# BMS_Controler.net
KiCad netlist of a schematic drawn in Altium Designer
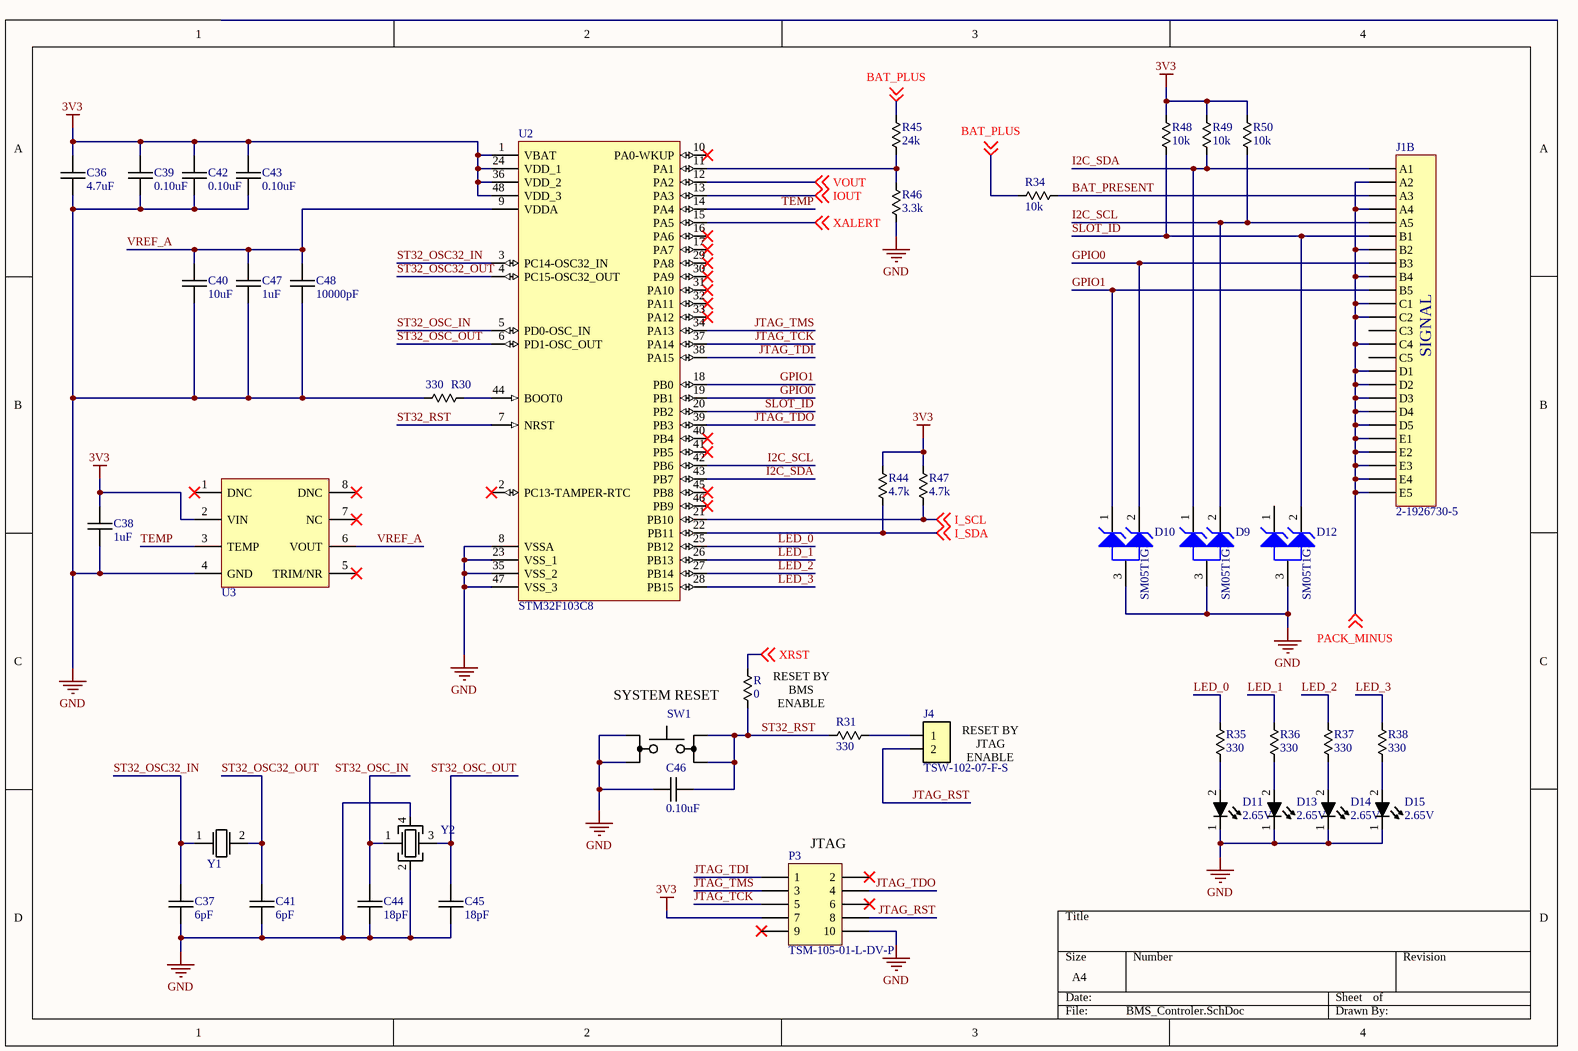
[diagram p0: BMS_Controler.SchDoc]

(export (version "E")
  (design (tool "Eeschema 10.0.6"))
  (components
    (comp (ref "C36")
      (value "4.7uF")
      (footprint "chip_0805")
      (description "CAP, 4.7uF, 10%, 25V, X7R, 0805")
      (fields (field (name "PART NUMBER") "CAP-00128") (field (name "TOLERANCE") "10%"))
      (libsource (lib "Capacitors$") (part "CAP-00128"))
    )
    (comp (ref "C37")
      (value "6pF")
      (footprint "chip_0603")
      (description "CAP, 6pF, ±10%, 50V, C0G, 0603")
      (fields (field (name "PART NUMBER") "CAP-00538") (field (name "TOLERANCE") "±10%"))
      (libsource (lib "Capacitors$") (part "CAP-00538"))
    )
    (comp (ref "C38")
      (value "1uF")
      (footprint "chip_0805")
      (description "CAP, 1uF, 10%, 50V, X7R, 0805")
      (fields (field (name "PART NUMBER") "CAP-00109") (field (name "TOLERANCE") "10%"))
      (libsource (lib "Capacitors$") (part "CAP-00109"))
    )
    (comp (ref "C39")
      (value "0.10uF")
      (footprint "chip_0805")
      (description "CAP, 0.10uF, 10%, 50V, X7R, 0805")
      (fields (field (name "PART NUMBER") "CAP-00072") (field (name "TOLERANCE") "10%"))
      (libsource (lib "Capacitors$") (part "CAP-00072"))
    )
    (comp (ref "C40")
      (value "10uF")
      (footprint "chip_0805")
      (description "CAP, 10uF, 10%, 10V, X7R, 0805")
      (fields (field (name "PART NUMBER") "CAP-00131") (field (name "TOLERANCE") "10%"))
      (libsource (lib "Capacitors$") (part "CAP-00131"))
    )
    (comp (ref "C41")
      (value "6pF")
      (footprint "chip_0603")
      (description "CAP, 6pF, ±10%, 50V, C0G, 0603")
      (fields (field (name "PART NUMBER") "CAP-00538") (field (name "TOLERANCE") "±10%"))
      (libsource (lib "Capacitors$") (part "CAP-00538"))
    )
    (comp (ref "C42")
      (value "0.10uF")
      (footprint "chip_0805")
      (description "CAP, 0.10uF, 10%, 50V, X7R, 0805")
      (fields (field (name "PART NUMBER") "CAP-00072") (field (name "TOLERANCE") "10%"))
      (libsource (lib "Capacitors$") (part "CAP-00072"))
    )
    (comp (ref "C43")
      (value "0.10uF")
      (footprint "chip_0805")
      (description "CAP, 0.10uF, 10%, 50V, X7R, 0805")
      (fields (field (name "PART NUMBER") "CAP-00072") (field (name "TOLERANCE") "10%"))
      (libsource (lib "Capacitors$") (part "CAP-00072"))
    )
    (comp (ref "C44")
      (value "18pF")
      (footprint "chip_0603")
      (description "CAP, 18pF, ±1%, 50V, C0G, 0603")
      (fields (field (name "PART NUMBER") "CAP-00417") (field (name "TOLERANCE") "±1%"))
      (libsource (lib "Capacitors$") (part "CAP-00417"))
    )
    (comp (ref "C45")
      (value "18pF")
      (footprint "chip_0603")
      (description "CAP, 18pF, ±1%, 50V, C0G, 0603")
      (fields (field (name "PART NUMBER") "CAP-00417") (field (name "TOLERANCE") "±1%"))
      (libsource (lib "Capacitors$") (part "CAP-00417"))
    )
    (comp (ref "C46")
      (value "0.10uF")
      (footprint "chip_0805")
      (description "CAP, 0.10uF, 10%, 50V, X7R, 0805")
      (fields (field (name "PART NUMBER") "CAP-00072") (field (name "TOLERANCE") "10%"))
      (libsource (lib "Capacitors$") (part "CAP-00072"))
    )
    (comp (ref "C47")
      (value "1uF")
      (footprint "chip_0805")
      (description "CAP, 1uF, 10%, 50V, X7R, 0805")
      (fields (field (name "PART NUMBER") "CAP-00109") (field (name "TOLERANCE") "10%"))
      (libsource (lib "Capacitors$") (part "CAP-00109"))
    )
    (comp (ref "C48")
      (value "10000pF")
      (footprint "chip_0805")
      (description "CAP, 10000pF, 10%, 25V, X7R, 0805")
      (fields (field (name "PART NUMBER") "CAP-00045") (field (name "TOLERANCE") "10%"))
      (libsource (lib "Capacitors$") (part "CAP-00045"))
    )
    (comp (ref "D9")
      (value "SM05T1G")
      (footprint "ONSC-SOT-23-3-318-08_V")
      (fields (field (name "MANUFACTURER") "On Semiconductor"))
      (libsource (lib "Altium Content Vault") (part "ONSC-K1K2A3-3"))
    )
    (comp (ref "D10")
      (value "SM05T1G")
      (footprint "ONSC-SOT-23-3-318-08_V")
      (fields (field (name "MANUFACTURER") "On Semiconductor"))
      (libsource (lib "Altium Content Vault") (part "ONSC-K1K2A3-3"))
    )
    (comp (ref "D11")
      (value "2.65V")
      (footprint "APA2107")
      (description "LED, Green, SMD Right-Angle, Low-Current, Kingbright HELI2 Series")
      (fields (field (name "PART NUMBER") "DIO-00083") (field (name "MANUFACTURER") "Kingbright"))
      (libsource (lib "Diodes$") (part "DIO-00083"))
    )
    (comp (ref "D12")
      (value "SM05T1G")
      (footprint "ONSC-SOT-23-3-318-08_V")
      (fields (field (name "MANUFACTURER") "On Semiconductor"))
      (libsource (lib "Altium Content Vault") (part "ONSC-K1K2A3-3"))
    )
    (comp (ref "D13")
      (value "2.65V")
      (footprint "APA2107")
      (description "LED, Green, SMD Right-Angle, Low-Current, Kingbright HELI2 Series")
      (fields (field (name "PART NUMBER") "DIO-00083") (field (name "MANUFACTURER") "Kingbright"))
      (libsource (lib "Diodes$") (part "DIO-00083"))
    )
    (comp (ref "D14")
      (value "2.65V")
      (footprint "APA2107")
      (description "LED, Green, SMD Right-Angle, Low-Current, Kingbright HELI2 Series")
      (fields (field (name "PART NUMBER") "DIO-00083") (field (name "MANUFACTURER") "Kingbright"))
      (libsource (lib "Diodes$") (part "DIO-00083"))
    )
    (comp (ref "D15")
      (value "2.65V")
      (footprint "APA2107")
      (description "LED, Green, SMD Right-Angle, Low-Current, Kingbright HELI2 Series")
      (fields (field (name "PART NUMBER") "DIO-00083") (field (name "MANUFACTURER") "Kingbright"))
      (libsource (lib "Diodes$") (part "DIO-00083"))
    )
    (comp (ref "J1")
      (value "2-1926730-5")
      (footprint "TE_CONN_2-1926730-5")
      (description "Backplane Header, Blades and Pins, Edge Mount Right Angle, 10 Power 25 Signal")
      (fields (field (name "PART NUMBER") "CONN-00093") (field (name "MANUFACTURER") "TE Connectivity"))
      (libsource (lib "Connectors$") (part "CONN-00093"))
    )
    (comp (ref "J4")
      (value "TSW-102-07-F-S")
      (footprint "HDDR_2x1_0")
      (description "Header, 2x1, 0.1\"")
      (fields (field (name "PART NUMBER") "CONN-00055") (field (name "MANUFACTURER") "Samtec"))
      (libsource (lib "Connectors$") (part "CONN-00055"))
    )
    (comp (ref "P3")
      (value "TSM-105-01-L-DV-P")
      (footprint "SAMTEC_SMD_HDDR_5x2")
      (description "Header, 5x2, 0.1\", SMD")
      (fields (field (name "PART NUMBER") "CONN-00071") (field (name "MANUFACTURER") "Samtec"))
      (libsource (lib "Connectors$") (part "CONN-00071"))
    )
    (comp (ref "R30")
      (value "330")
      (footprint "chip_0805")
      (description "RES SMD 330 OHM 1% 1/8W 0805")
      (fields (field (name "PART NUMBER") "RES-00222") (field (name "TOLERANCE") "1%"))
      (libsource (lib "Resistors$") (part "RES-00222"))
    )
    (comp (ref "R31")
      (value "330")
      (footprint "chip_0805")
      (description "RES SMD 330 OHM 1% 1/8W 0805")
      (fields (field (name "PART NUMBER") "RES-00222") (field (name "TOLERANCE") "1%"))
      (libsource (lib "Resistors$") (part "RES-00222"))
    )
    (comp (ref "R34")
      (value "10k")
      (footprint "chip_0805")
      (description "RES SMD 10K OHM 1% 1/8W 0805")
      (fields (field (name "PART NUMBER") "RES-00307") (field (name "TOLERANCE") "1%"))
      (libsource (lib "Resistors$") (part "RES-00307"))
    )
    (comp (ref "R35")
      (value "330")
      (footprint "chip_0805")
      (description "RES SMD 330 OHM 1% 1/8W 0805")
      (fields (field (name "PART NUMBER") "RES-00222") (field (name "TOLERANCE") "1%"))
      (libsource (lib "Resistors$") (part "RES-00222"))
    )
    (comp (ref "R36")
      (value "330")
      (footprint "chip_0805")
      (description "RES SMD 330 OHM 1% 1/8W 0805")
      (fields (field (name "PART NUMBER") "RES-00222") (field (name "TOLERANCE") "1%"))
      (libsource (lib "Resistors$") (part "RES-00222"))
    )
    (comp (ref "R37")
      (value "330")
      (footprint "chip_0805")
      (description "RES SMD 330 OHM 1% 1/8W 0805")
      (fields (field (name "PART NUMBER") "RES-00222") (field (name "TOLERANCE") "1%"))
      (libsource (lib "Resistors$") (part "RES-00222"))
    )
    (comp (ref "R38")
      (value "330")
      (footprint "chip_0805")
      (description "RES SMD 330 OHM 1% 1/8W 0805")
      (fields (field (name "PART NUMBER") "RES-00222") (field (name "TOLERANCE") "1%"))
      (libsource (lib "Resistors$") (part "RES-00222"))
    )
    (comp (ref "R43")
      (value "0")
      (footprint "chip_0805")
      (description "RES SMD 0 OHM 1/8W 0805 Thick Film")
      (fields (field (name "PART NUMBER") "RES-00720") (field (name "TOLERANCE") "Jumper"))
      (libsource (lib "Resistors$") (part "RES-00720"))
    )
    (comp (ref "R44")
      (value "4.7k")
      (footprint "chip_0805")
      (description "RES SMD 4.7K OHM 1% 1/8W 0805")
      (fields (field (name "PART NUMBER") "RES-00471") (field (name "TOLERANCE") "1%"))
      (libsource (lib "Resistors$") (part "RES-00471"))
    )
    (comp (ref "R45")
      (value "24k")
      (footprint "chip_0805")
      (description "RES SMD 24K OHM 1% 1/8W 0805")
      (fields (field (name "PART NUMBER") "RES-00400") (field (name "TOLERANCE") "1%"))
      (libsource (lib "Resistors$") (part "RES-00400"))
    )
    (comp (ref "R46")
      (value "3.3k")
      (footprint "chip_0805")
      (description "RES SMD 3.3K OHM 1% 1/8W 0805")
      (fields (field (name "PART NUMBER") "RES-00420") (field (name "TOLERANCE") "1%"))
      (libsource (lib "Resistors$") (part "RES-00420"))
    )
    (comp (ref "R47")
      (value "4.7k")
      (footprint "chip_0805")
      (description "RES SMD 4.7K OHM 1% 1/8W 0805")
      (fields (field (name "PART NUMBER") "RES-00471") (field (name "TOLERANCE") "1%"))
      (libsource (lib "Resistors$") (part "RES-00471"))
    )
    (comp (ref "R48")
      (value "10k")
      (footprint "chip_0805")
      (description "RES SMD 10K OHM 1% 1/8W 0805")
      (fields (field (name "PART NUMBER") "RES-00307") (field (name "TOLERANCE") "1%"))
      (libsource (lib "Resistors$") (part "RES-00307"))
    )
    (comp (ref "R49")
      (value "10k")
      (footprint "chip_0805")
      (description "RES SMD 10K OHM 1% 1/8W 0805")
      (fields (field (name "PART NUMBER") "RES-00307") (field (name "TOLERANCE") "1%"))
      (libsource (lib "Resistors$") (part "RES-00307"))
    )
    (comp (ref "R50")
      (value "10k")
      (footprint "chip_0805")
      (description "RES SMD 10K OHM 1% 1/8W 0805")
      (fields (field (name "PART NUMBER") "RES-00307") (field (name "TOLERANCE") "1%"))
      (libsource (lib "Resistors$") (part "RES-00307"))
    )
    (comp (ref "SW1")
      (value "SW_1P1T_2")
      (footprint "B3FS-1000")
      (description "Switch, SPST-NO, Tactile, 6.3x6.0mm, SMD, 50mA 24VDC")
      (fields (field (name "PART NUMBER") "MISC-00042") (field (name "MANUFACTURER") "Omron"))
      (libsource (lib "Misc$") (part "MISC-00042"))
    )
    (comp (ref "U2")
      (value "STM32F103C8")
      (footprint "LQFP48_0")
      (description "STM32 M3, LQFP-48")
      (fields (field (name "PART NUMBER") "UCTRL-00008") (field (name "MANUFACTURER") "ST"))
      (libsource (lib "Microcontrollers$") (part "UCTRL-00008"))
    )
    (comp (ref "U3")
      (value "REF50xx")
      (footprint "SO-8_1")
      (description "IC, Voltage Reference, 2.5V, 3ppm/°C, REF5020")
      (fields (field (name "PART NUMBER") "ANLG-00055") (field (name "MANUFACTURER") "TI"))
      (libsource (lib "Analog$") (part "ANLG-00055"))
    )
    (comp (ref "Y1")
      (value "osc_xtal_2p_0")
      (footprint "ABS25_OSC")
      (description "XTAL, 32.768kHz, 6pF, 20ppm")
      (fields (field (name "PART NUMBER") "OSC-00003") (field (name "TOLERANCE") "20ppm"))
      (libsource (lib "Oscillators$") (part "OSC-00003"))
    )
    (comp (ref "Y2")
      (value "osc_xtal_4p_1-3")
      (footprint "ECX-53B")
      (description "XTAL, 8MHz, 10pF, 10ppm")
      (fields (field (name "PART NUMBER") "OSC-00006") (field (name "TOLERANCE") "10ppm"))
      (libsource (lib "Oscillators$") (part "OSC-00006"))
    )
  )
  (nets
    (net (code "1") (name "/BAT_PRESENT") (class "Default")
      (node (ref "J1") (pin "A3") (pinfunction "A3_A3") (pintype "passive"))
      (node (ref "R34") (pin "2") (pinfunction "2_2") (pintype "passive"))
    )
    (net (code "2") (name "/GPIO0") (class "Default")
      (node (ref "D10") (pin "2") (pinfunction "K2_2") (pintype "passive"))
      (node (ref "J1") (pin "B3") (pinfunction "B3_B3") (pintype "passive"))
      (node (ref "U2") (pin "19") (pinfunction "PB1_19") (pintype "bidirectional"))
    )
    (net (code "3") (name "/GPIO1") (class "Default")
      (node (ref "D10") (pin "1") (pinfunction "K1_1") (pintype "passive"))
      (node (ref "J1") (pin "B5") (pinfunction "B5_B5") (pintype "passive"))
      (node (ref "U2") (pin "18") (pinfunction "PB0_18") (pintype "bidirectional"))
    )
    (net (code "4") (name "/I2C_SCL") (class "Default")
      (node (ref "D9") (pin "2") (pinfunction "K2_2") (pintype "passive"))
      (node (ref "J1") (pin "A5") (pinfunction "A5_A5") (pintype "passive"))
      (node (ref "R50") (pin "1") (pinfunction "1_1") (pintype "passive"))
      (node (ref "U2") (pin "42") (pinfunction "PB6_42") (pintype "bidirectional"))
    )
    (net (code "5") (name "/I2C_SDA") (class "Default")
      (node (ref "D9") (pin "1") (pinfunction "K1_1") (pintype "passive"))
      (node (ref "J1") (pin "A1") (pinfunction "A1_A1") (pintype "passive"))
      (node (ref "R49") (pin "1") (pinfunction "1_1") (pintype "passive"))
      (node (ref "U2") (pin "43") (pinfunction "PB7_43") (pintype "bidirectional"))
    )
    (net (code "6") (name "/JTAG_RST") (class "Default")
      (node (ref "J4") (pin "2") (pinfunction "2_2") (pintype "passive"))
      (node (ref "P3") (pin "8") (pinfunction "8_8") (pintype "passive"))
    )
    (net (code "7") (name "/JTAG_TCK") (class "Default")
      (node (ref "P3") (pin "5") (pinfunction "5_5") (pintype "passive"))
      (node (ref "U2") (pin "37") (pinfunction "PA14_37") (pintype "bidirectional"))
    )
    (net (code "8") (name "/JTAG_TDI") (class "Default")
      (node (ref "P3") (pin "1") (pinfunction "1_1") (pintype "passive"))
      (node (ref "U2") (pin "38") (pinfunction "PA15_38") (pintype "bidirectional"))
    )
    (net (code "9") (name "/JTAG_TDO") (class "Default")
      (node (ref "P3") (pin "4") (pinfunction "4_4") (pintype "passive"))
      (node (ref "U2") (pin "39") (pinfunction "PB3_39") (pintype "bidirectional"))
    )
    (net (code "10") (name "/JTAG_TMS") (class "Default")
      (node (ref "P3") (pin "3") (pinfunction "3_3") (pintype "passive"))
      (node (ref "U2") (pin "34") (pinfunction "PA13_34") (pintype "bidirectional"))
    )
    (net (code "11") (name "/LED_0") (class "Default")
      (node (ref "R35") (pin "1") (pinfunction "1_1") (pintype "passive"))
      (node (ref "U2") (pin "25") (pinfunction "PB12_25") (pintype "bidirectional"))
    )
    (net (code "12") (name "/LED_1") (class "Default")
      (node (ref "R36") (pin "1") (pinfunction "1_1") (pintype "passive"))
      (node (ref "U2") (pin "26") (pinfunction "PB13_26") (pintype "bidirectional"))
    )
    (net (code "13") (name "/LED_2") (class "Default")
      (node (ref "R37") (pin "1") (pinfunction "1_1") (pintype "passive"))
      (node (ref "U2") (pin "27") (pinfunction "PB14_27") (pintype "bidirectional"))
    )
    (net (code "14") (name "/LED_3") (class "Default")
      (node (ref "R38") (pin "1") (pinfunction "1_1") (pintype "passive"))
      (node (ref "U2") (pin "28") (pinfunction "PB15_28") (pintype "bidirectional"))
    )
    (net (code "15") (name "/SLOT_ID") (class "Default")
      (node (ref "D12") (pin "2") (pinfunction "K2_2") (pintype "passive"))
      (node (ref "J1") (pin "B1") (pinfunction "B1_B1") (pintype "passive"))
      (node (ref "R48") (pin "1") (pinfunction "1_1") (pintype "passive"))
      (node (ref "U2") (pin "20") (pinfunction "PB2_20") (pintype "bidirectional"))
    )
    (net (code "16") (name "/ST32_OSC32_IN") (class "Default")
      (node (ref "C37") (pin "1") (pinfunction "1_1") (pintype "passive"))
      (node (ref "U2") (pin "3") (pinfunction "PC14-OSC32_IN_3") (pintype "bidirectional"))
      (node (ref "Y1") (pin "1") (pinfunction "20_1") (pintype "passive"))
    )
    (net (code "17") (name "/ST32_OSC32_OUT") (class "Default")
      (node (ref "C41") (pin "2") (pinfunction "2_2") (pintype "passive"))
      (node (ref "U2") (pin "4") (pinfunction "PC15-OSC32_OUT_4") (pintype "bidirectional"))
      (node (ref "Y1") (pin "2") (pinfunction "20_2") (pintype "passive"))
    )
    (net (code "18") (name "/ST32_OSC_IN") (class "Default")
      (node (ref "C44") (pin "1") (pinfunction "1_1") (pintype "passive"))
      (node (ref "U2") (pin "5") (pinfunction "PD0-OSC_IN_5") (pintype "bidirectional"))
      (node (ref "Y2") (pin "1") (pinfunction "1_1") (pintype "passive"))
    )
    (net (code "19") (name "/ST32_OSC_OUT") (class "Default")
      (node (ref "C45") (pin "1") (pinfunction "1_1") (pintype "passive"))
      (node (ref "U2") (pin "6") (pinfunction "PD1-OSC_OUT_6") (pintype "bidirectional"))
      (node (ref "Y2") (pin "3") (pinfunction "3_3") (pintype "passive"))
    )
    (net (code "20") (name "/ST32_RST") (class "Default")
      (node (ref "C46") (pin "2") (pinfunction "2_2") (pintype "passive"))
      (node (ref "R31") (pin "1") (pinfunction "1_1") (pintype "passive"))
      (node (ref "R43") (pin "2") (pinfunction "2_2") (pintype "passive"))
      (node (ref "SW1") (pin "3") (pinfunction "3_3") (pintype "passive"))
      (node (ref "SW1") (pin "4") (pinfunction "4_4") (pintype "passive"))
      (node (ref "U2") (pin "7") (pinfunction "NRST_7") (pintype "input"))
    )
    (net (code "21") (name "/TEMP") (class "Default")
      (node (ref "U2") (pin "14") (pinfunction "PA4_14") (pintype "bidirectional"))
      (node (ref "U3") (pin "3") (pinfunction "TEMP_3") (pintype "power_in"))
    )
    (net (code "22") (name "/VREF_A") (class "Default")
      (node (ref "C40") (pin "1") (pinfunction "1_1") (pintype "passive"))
      (node (ref "C47") (pin "2") (pinfunction "2_2") (pintype "passive"))
      (node (ref "C48") (pin "1") (pinfunction "1_1") (pintype "passive"))
      (node (ref "U2") (pin "9") (pinfunction "VDDA_9") (pintype "power_in"))
      (node (ref "U3") (pin "6") (pinfunction "VOUT_6") (pintype "power_in"))
    )
    (net (code "23") (name "3V3") (class "Default")
      (node (ref "C36") (pin "2") (pinfunction "2_2") (pintype "passive"))
      (node (ref "C38") (pin "2") (pinfunction "2_2") (pintype "passive"))
      (node (ref "C39") (pin "1") (pinfunction "1_1") (pintype "passive"))
      (node (ref "C42") (pin "1") (pinfunction "1_1") (pintype "passive"))
      (node (ref "C43") (pin "1") (pinfunction "1_1") (pintype "passive"))
      (node (ref "P3") (pin "7") (pinfunction "7_7") (pintype "passive"))
      (node (ref "R44") (pin "1") (pinfunction "1_1") (pintype "passive"))
      (node (ref "R47") (pin "1") (pinfunction "1_1") (pintype "passive"))
      (node (ref "R48") (pin "2") (pinfunction "2_2") (pintype "passive"))
      (node (ref "R49") (pin "2") (pinfunction "2_2") (pintype "passive"))
      (node (ref "R50") (pin "2") (pinfunction "2_2") (pintype "passive"))
      (node (ref "U2") (pin "1") (pinfunction "VBAT_1") (pintype "passive"))
      (node (ref "U2") (pin "24") (pinfunction "VDD_1_24") (pintype "power_in"))
      (node (ref "U2") (pin "36") (pinfunction "VDD_2_36") (pintype "power_in"))
      (node (ref "U2") (pin "48") (pinfunction "VDD_3_48") (pintype "power_in"))
      (node (ref "U3") (pin "2") (pinfunction "VIN_2") (pintype "power_in"))
    )
    (net (code "24") (name "BAT_PLUS") (class "Default")
      (node (ref "R34") (pin "1") (pinfunction "1_1") (pintype "passive"))
      (node (ref "R45") (pin "1") (pinfunction "1_1") (pintype "passive"))
    )
    (net (code "25") (name "GND") (class "Default")
      (node (ref "C36") (pin "1") (pinfunction "1_1") (pintype "passive"))
      (node (ref "C37") (pin "2") (pinfunction "2_2") (pintype "passive"))
      (node (ref "C38") (pin "1") (pinfunction "1_1") (pintype "passive"))
      (node (ref "C39") (pin "2") (pinfunction "2_2") (pintype "passive"))
      (node (ref "C40") (pin "2") (pinfunction "2_2") (pintype "passive"))
      (node (ref "C41") (pin "1") (pinfunction "1_1") (pintype "passive"))
      (node (ref "C42") (pin "2") (pinfunction "2_2") (pintype "passive"))
      (node (ref "C43") (pin "2") (pinfunction "2_2") (pintype "passive"))
      (node (ref "C44") (pin "2") (pinfunction "2_2") (pintype "passive"))
      (node (ref "C45") (pin "2") (pinfunction "2_2") (pintype "passive"))
      (node (ref "C46") (pin "1") (pinfunction "1_1") (pintype "passive"))
      (node (ref "C47") (pin "1") (pinfunction "1_1") (pintype "passive"))
      (node (ref "C48") (pin "2") (pinfunction "2_2") (pintype "passive"))
      (node (ref "D10") (pin "3") (pinfunction "A_3") (pintype "passive"))
      (node (ref "D11") (pin "1") (pinfunction "1_1") (pintype "passive"))
      (node (ref "D12") (pin "3") (pinfunction "A_3") (pintype "passive"))
      (node (ref "D13") (pin "1") (pinfunction "1_1") (pintype "passive"))
      (node (ref "D14") (pin "1") (pinfunction "1_1") (pintype "passive"))
      (node (ref "D15") (pin "1") (pinfunction "1_1") (pintype "passive"))
      (node (ref "D9") (pin "3") (pinfunction "A_3") (pintype "passive"))
      (node (ref "P3") (pin "10") (pinfunction "10_10") (pintype "passive"))
      (node (ref "R30") (pin "1") (pinfunction "1_1") (pintype "passive"))
      (node (ref "R46") (pin "2") (pinfunction "2_2") (pintype "passive"))
      (node (ref "SW1") (pin "1") (pinfunction "1_1") (pintype "passive"))
      (node (ref "SW1") (pin "2") (pinfunction "2_2") (pintype "passive"))
      (node (ref "U2") (pin "23") (pinfunction "VSS_1_23") (pintype "power_in"))
      (node (ref "U2") (pin "35") (pinfunction "VSS_2_35") (pintype "power_in"))
      (node (ref "U2") (pin "47") (pinfunction "VSS_3_47") (pintype "power_in"))
      (node (ref "U2") (pin "8") (pinfunction "VSSA_8") (pintype "power_in"))
      (node (ref "U3") (pin "4") (pinfunction "GND_4") (pintype "power_in"))
      (node (ref "Y2") (pin "2") (pinfunction "GND_2") (pintype "passive"))
      (node (ref "Y2") (pin "4") (pinfunction "GND_4") (pintype "passive"))
    )
    (net (code "26") (name "IOUT") (class "Default")
      (node (ref "U2") (pin "13") (pinfunction "PA3_13") (pintype "bidirectional"))
    )
    (net (code "27") (name "I_SCL") (class "Default")
      (node (ref "R47") (pin "2") (pinfunction "2_2") (pintype "passive"))
      (node (ref "U2") (pin "21") (pinfunction "PB10_21") (pintype "bidirectional"))
    )
    (net (code "28") (name "I_SDA") (class "Default")
      (node (ref "R44") (pin "2") (pinfunction "2_2") (pintype "passive"))
      (node (ref "U2") (pin "22") (pinfunction "PB11_22") (pintype "bidirectional"))
    )
    (net (code "29") (name "Net-(D11-Pad2)") (class "Default")
      (node (ref "D11") (pin "2") (pinfunction "2_2") (pintype "passive"))
      (node (ref "R35") (pin "2") (pinfunction "2_2") (pintype "passive"))
    )
    (net (code "30") (name "Net-(D13-Pad2)") (class "Default")
      (node (ref "D13") (pin "2") (pinfunction "2_2") (pintype "passive"))
      (node (ref "R36") (pin "2") (pinfunction "2_2") (pintype "passive"))
    )
    (net (code "31") (name "Net-(D14-Pad2)") (class "Default")
      (node (ref "D14") (pin "2") (pinfunction "2_2") (pintype "passive"))
      (node (ref "R37") (pin "2") (pinfunction "2_2") (pintype "passive"))
    )
    (net (code "32") (name "Net-(D15-Pad2)") (class "Default")
      (node (ref "D15") (pin "2") (pinfunction "2_2") (pintype "passive"))
      (node (ref "R38") (pin "2") (pinfunction "2_2") (pintype "passive"))
    )
    (net (code "33") (name "Net-(J4-Pad1)") (class "Default")
      (node (ref "J4") (pin "1") (pinfunction "1_1") (pintype "passive"))
      (node (ref "R31") (pin "2") (pinfunction "2_2") (pintype "passive"))
    )
    (net (code "34") (name "Net-(U2-BOOT0)") (class "Default")
      (node (ref "R30") (pin "2") (pinfunction "2_2") (pintype "passive"))
      (node (ref "U2") (pin "44") (pinfunction "BOOT0_44") (pintype "input"))
    )
    (net (code "35") (name "Net-(U2-PA1)") (class "Default")
      (node (ref "R45") (pin "2") (pinfunction "2_2") (pintype "passive"))
      (node (ref "R46") (pin "1") (pinfunction "1_1") (pintype "passive"))
      (node (ref "U2") (pin "11") (pinfunction "PA1_11") (pintype "bidirectional"))
    )
    (net (code "36") (name "PACK_MINUS") (class "Default")
      (node (ref "J1") (pin "A2") (pinfunction "A2_A2") (pintype "passive"))
      (node (ref "J1") (pin "A4") (pinfunction "A4_A4") (pintype "passive"))
      (node (ref "J1") (pin "B2") (pinfunction "B2_B2") (pintype "passive"))
      (node (ref "J1") (pin "B4") (pinfunction "B4_B4") (pintype "passive"))
      (node (ref "J1") (pin "C1") (pinfunction "C1_C1") (pintype "passive"))
      (node (ref "J1") (pin "C2") (pinfunction "C2_C2") (pintype "passive"))
      (node (ref "J1") (pin "C4") (pinfunction "C4_C4") (pintype "passive"))
      (node (ref "J1") (pin "D1") (pinfunction "D1_D1") (pintype "passive"))
      (node (ref "J1") (pin "D2") (pinfunction "D2_D2") (pintype "passive"))
      (node (ref "J1") (pin "D3") (pinfunction "D3_D3") (pintype "passive"))
      (node (ref "J1") (pin "D4") (pinfunction "D4_D4") (pintype "passive"))
      (node (ref "J1") (pin "D5") (pinfunction "D5_D5") (pintype "passive"))
      (node (ref "J1") (pin "E1") (pinfunction "E1_E1") (pintype "passive"))
      (node (ref "J1") (pin "E2") (pinfunction "E2_E2") (pintype "passive"))
      (node (ref "J1") (pin "E3") (pinfunction "E3_E3") (pintype "passive"))
      (node (ref "J1") (pin "E4") (pinfunction "E4_E4") (pintype "passive"))
      (node (ref "J1") (pin "E5") (pinfunction "E5_E5") (pintype "passive"))
    )
    (net (code "37") (name "VOUT") (class "Default")
      (node (ref "U2") (pin "12") (pinfunction "PA2_12") (pintype "bidirectional"))
    )
    (net (code "38") (name "XALERT") (class "Default")
      (node (ref "U2") (pin "15") (pinfunction "PA5_15") (pintype "bidirectional"))
    )
    (net (code "39") (name "XRST") (class "Default")
      (node (ref "R43") (pin "1") (pinfunction "1_1") (pintype "passive"))
    )
    (net (code "40") (name "unconnected-(D12-K1-Pad1)") (class "Default")
      (node (ref "D12") (pin "1") (pinfunction "K1_1") (pintype "passive"))
    )
    (net (code "41") (name "unconnected-(J1-PadC3)") (class "Default")
      (node (ref "J1") (pin "C3") (pinfunction "C3_C3") (pintype "passive"))
    )
    (net (code "42") (name "unconnected-(J1-PadC5)") (class "Default")
      (node (ref "J1") (pin "C5") (pinfunction "C5_C5") (pintype "passive"))
    )
    (net (code "43") (name "unconnected-(P3-Pad2)") (class "Default")
      (node (ref "P3") (pin "2") (pinfunction "2_2") (pintype "passive+no_connect"))
    )
    (net (code "44") (name "unconnected-(P3-Pad6)") (class "Default")
      (node (ref "P3") (pin "6") (pinfunction "6_6") (pintype "passive+no_connect"))
    )
    (net (code "45") (name "unconnected-(P3-Pad9)") (class "Default")
      (node (ref "P3") (pin "9") (pinfunction "9_9") (pintype "passive+no_connect"))
    )
    (net (code "46") (name "unconnected-(U2-PA0-WKUP-Pad10)") (class "Default")
      (node (ref "U2") (pin "10") (pinfunction "PA0-WKUP_10") (pintype "bidirectional+no_connect"))
    )
    (net (code "47") (name "unconnected-(U2-PA6-Pad16)") (class "Default")
      (node (ref "U2") (pin "16") (pinfunction "PA6_16") (pintype "bidirectional+no_connect"))
    )
    (net (code "48") (name "unconnected-(U2-PA7-Pad17)") (class "Default")
      (node (ref "U2") (pin "17") (pinfunction "PA7_17") (pintype "bidirectional+no_connect"))
    )
    (net (code "49") (name "unconnected-(U2-PA8-Pad29)") (class "Default")
      (node (ref "U2") (pin "29") (pinfunction "PA8_29") (pintype "bidirectional+no_connect"))
    )
    (net (code "50") (name "unconnected-(U2-PA9-Pad30)") (class "Default")
      (node (ref "U2") (pin "30") (pinfunction "PA9_30") (pintype "bidirectional+no_connect"))
    )
    (net (code "51") (name "unconnected-(U2-PA10-Pad31)") (class "Default")
      (node (ref "U2") (pin "31") (pinfunction "PA10_31") (pintype "bidirectional+no_connect"))
    )
    (net (code "52") (name "unconnected-(U2-PA11-Pad32)") (class "Default")
      (node (ref "U2") (pin "32") (pinfunction "PA11_32") (pintype "bidirectional+no_connect"))
    )
    (net (code "53") (name "unconnected-(U2-PA12-Pad33)") (class "Default")
      (node (ref "U2") (pin "33") (pinfunction "PA12_33") (pintype "bidirectional+no_connect"))
    )
    (net (code "54") (name "unconnected-(U2-PB4-Pad40)") (class "Default")
      (node (ref "U2") (pin "40") (pinfunction "PB4_40") (pintype "bidirectional+no_connect"))
    )
    (net (code "55") (name "unconnected-(U2-PB5-Pad41)") (class "Default")
      (node (ref "U2") (pin "41") (pinfunction "PB5_41") (pintype "bidirectional+no_connect"))
    )
    (net (code "56") (name "unconnected-(U2-PB8-Pad45)") (class "Default")
      (node (ref "U2") (pin "45") (pinfunction "PB8_45") (pintype "bidirectional+no_connect"))
    )
    (net (code "57") (name "unconnected-(U2-PB9-Pad46)") (class "Default")
      (node (ref "U2") (pin "46") (pinfunction "PB9_46") (pintype "bidirectional+no_connect"))
    )
    (net (code "58") (name "unconnected-(U2-PC13-TAMPER-RTC-Pad2)") (class "Default")
      (node (ref "U2") (pin "2") (pinfunction "PC13-TAMPER-RTC_2") (pintype "bidirectional+no_connect"))
    )
    (net (code "59") (name "unconnected-(U3-DNC-Pad1)") (class "Default")
      (node (ref "U3") (pin "1") (pinfunction "DNC_1") (pintype "power_in+no_connect"))
    )
    (net (code "60") (name "unconnected-(U3-DNC-Pad8)") (class "Default")
      (node (ref "U3") (pin "8") (pinfunction "DNC_8") (pintype "power_in+no_connect"))
    )
    (net (code "61") (name "unconnected-(U3-NC-Pad7)") (class "Default")
      (node (ref "U3") (pin "7") (pinfunction "NC_7") (pintype "power_in+no_connect"))
    )
    (net (code "62") (name "unconnected-(U3-TRIM{slash}NR-Pad5)") (class "Default")
      (node (ref "U3") (pin "5") (pinfunction "TRIM/NR_5") (pintype "power_in+no_connect"))
    )
  )
)
